# BREAKOUT328.net
KiCad netlist of a schematic drawn in EAGLE
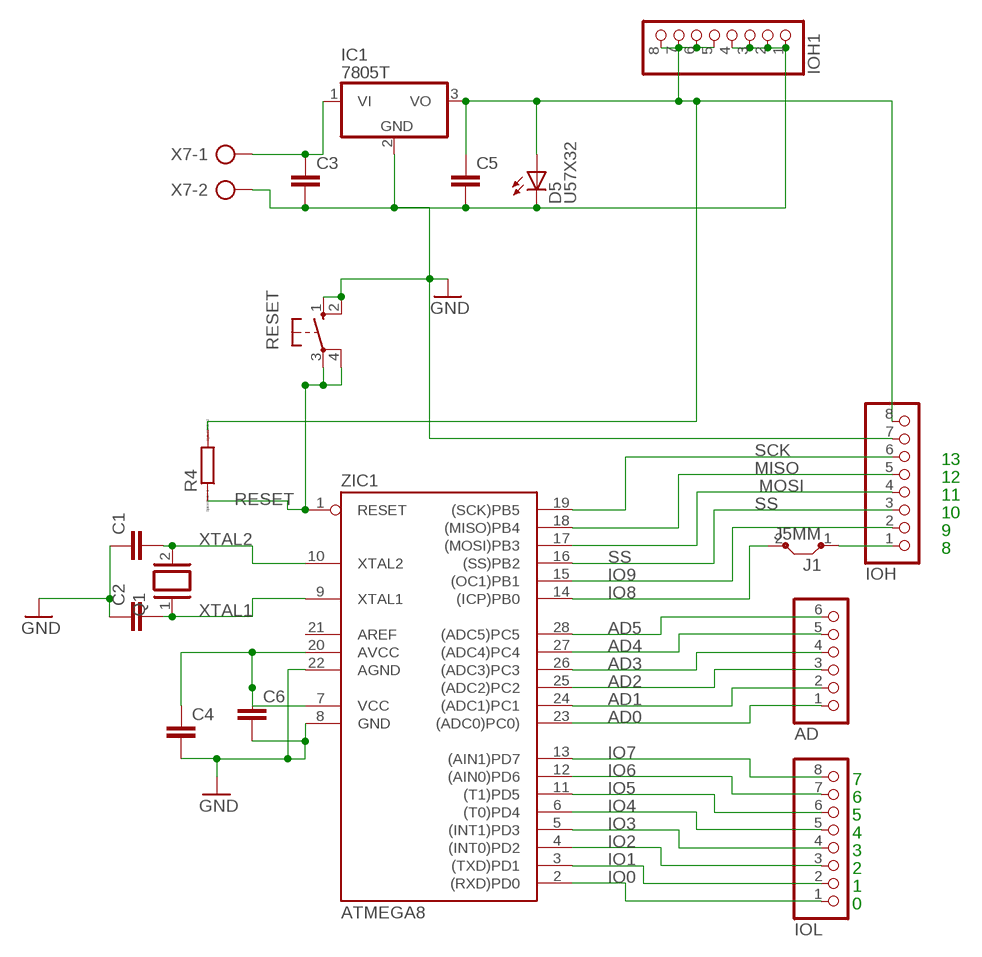
[diagram p0: schematic, sheet 1]

(export (version "E")
  (design (tool "Eeschema 10.0.6"))
  (components
    (comp (ref "AD")
      (value "PINHD-1X6")
      (footprint "eagle-import:1X06")
      (libsource (lib "eagle-import") (part "PINHD-1X6"))
    )
    (comp (ref "C1")
      (value "C2.5/6")
      (footprint "eagle-import:C2.5-6")
      (libsource (lib "eagle-import") (part "C2.5/6"))
    )
    (comp (ref "C2")
      (value "C2.5/6")
      (footprint "eagle-import:C2.5-6")
      (libsource (lib "eagle-import") (part "C2.5/6"))
    )
    (comp (ref "C3")
      (value "C2.5/4")
      (footprint "eagle-import:C2.5-4")
      (libsource (lib "eagle-import") (part "C2.5/4"))
    )
    (comp (ref "C4")
      (value "C2.5/4")
      (footprint "eagle-import:C2.5-4")
      (libsource (lib "eagle-import") (part "C2.5/4"))
    )
    (comp (ref "C5")
      (value "C2.5/4")
      (footprint "eagle-import:C2.5-4")
      (libsource (lib "eagle-import") (part "C2.5/4"))
    )
    (comp (ref "C6")
      (value "C2.5/4")
      (footprint "eagle-import:C2.5-4")
      (libsource (lib "eagle-import") (part "C2.5/4"))
    )
    (comp (ref "D5")
      (value "U57X32")
      (footprint "eagle-import:U57X32")
      (libsource (lib "eagle-import") (part "U57X32"))
    )
    (comp (ref "IC1")
      (value "7805T")
      (footprint "eagle-import:TO220H")
      (libsource (lib "eagle-import") (part "78T05"))
    )
    (comp (ref "IOH")
      (value "PINHD-1X8")
      (footprint "eagle-import:1X08")
      (libsource (lib "eagle-import") (part "PINHD-1X8"))
    )
    (comp (ref "IOH1")
      (value "PINHD-1X8")
      (footprint "eagle-import:1X08")
      (libsource (lib "eagle-import") (part "PINHD-1X8"))
    )
    (comp (ref "IOL")
      (value "PINHD-1X8")
      (footprint "eagle-import:1X08")
      (libsource (lib "eagle-import") (part "PINHD-1X8"))
    )
    (comp (ref "J1")
      (value "J5MM")
      (footprint "eagle-import:05")
      (libsource (lib "eagle-import") (part "J5MM"))
    )
    (comp (ref "Q1")
      (value "XTAL/S")
      (footprint "eagle-import:QS")
      (libsource (lib "eagle-import") (part "XTAL/S"))
    )
    (comp (ref "R4")
      (value "R0207/10")
      (footprint "eagle-import:0207_10")
      (libsource (lib "eagle-import") (part "R0207/10"))
    )
    (comp (ref "RESET")
      (value "10-XX")
      (footprint "eagle-import:B3F-10XX")
      (fields (field (name "MPN") "B3F-1000"))
      (libsource (lib "eagle-import") (part "10-XX"))
    )
    (comp (ref "X7")
      (value "AK500/2-H")
      (footprint "eagle-import:AK500_2-H")
      (libsource (lib "eagle-import") (part "AK500/2-H"))
    )
    (comp (ref "ZIC1")
      (value "ATMEGA8")
      (footprint "eagle-import:DIL28-3")
      (libsource (lib "eagle-import") (part "AT90S4433P"))
    )
  )
  (nets
    (net (code "1") (name "/AD0") (class "Default")
      (node (ref "AD") (pin "1") (pinfunction "1_1") (pintype "passive"))
      (node (ref "ZIC1") (pin "23") (pinfunction "(ADC0)PC0)_23") (pintype "bidirectional"))
    )
    (net (code "2") (name "/AD1") (class "Default")
      (node (ref "AD") (pin "2") (pinfunction "2_2") (pintype "passive"))
      (node (ref "ZIC1") (pin "24") (pinfunction "(ADC1)PC1_24") (pintype "bidirectional"))
    )
    (net (code "3") (name "/AD2") (class "Default")
      (node (ref "AD") (pin "3") (pinfunction "3_3") (pintype "passive"))
      (node (ref "ZIC1") (pin "25") (pinfunction "(ADC2)PC2_25") (pintype "bidirectional"))
    )
    (net (code "4") (name "/AD3") (class "Default")
      (node (ref "AD") (pin "4") (pinfunction "4_4") (pintype "passive"))
      (node (ref "ZIC1") (pin "26") (pinfunction "(ADC3)PC3_26") (pintype "bidirectional"))
    )
    (net (code "5") (name "/AD4") (class "Default")
      (node (ref "AD") (pin "5") (pinfunction "5_5") (pintype "passive"))
      (node (ref "ZIC1") (pin "27") (pinfunction "(ADC4)PC4_27") (pintype "bidirectional"))
    )
    (net (code "6") (name "/AD5") (class "Default")
      (node (ref "AD") (pin "6") (pinfunction "6_6") (pintype "passive"))
      (node (ref "ZIC1") (pin "28") (pinfunction "(ADC5)PC5_28") (pintype "bidirectional"))
    )
    (net (code "7") (name "/IO0") (class "Default")
      (node (ref "IOL") (pin "1") (pinfunction "1_1") (pintype "passive"))
      (node (ref "ZIC1") (pin "2") (pinfunction "(RXD)PD0_2") (pintype "bidirectional"))
    )
    (net (code "8") (name "/IO1") (class "Default")
      (node (ref "IOL") (pin "2") (pinfunction "2_2") (pintype "passive"))
      (node (ref "ZIC1") (pin "3") (pinfunction "(TXD)PD1_3") (pintype "bidirectional"))
    )
    (net (code "9") (name "/IO2") (class "Default")
      (node (ref "IOL") (pin "3") (pinfunction "3_3") (pintype "passive"))
      (node (ref "ZIC1") (pin "4") (pinfunction "(INT0)PD2_4") (pintype "bidirectional"))
    )
    (net (code "10") (name "/IO3") (class "Default")
      (node (ref "IOL") (pin "4") (pinfunction "4_4") (pintype "passive"))
      (node (ref "ZIC1") (pin "5") (pinfunction "(INT1)PD3_5") (pintype "bidirectional"))
    )
    (net (code "11") (name "/IO4") (class "Default")
      (node (ref "IOL") (pin "5") (pinfunction "5_5") (pintype "passive"))
      (node (ref "ZIC1") (pin "6") (pinfunction "(T0)PD4_6") (pintype "bidirectional"))
    )
    (net (code "12") (name "/IO5") (class "Default")
      (node (ref "IOL") (pin "6") (pinfunction "6_6") (pintype "passive"))
      (node (ref "ZIC1") (pin "11") (pinfunction "(T1)PD5_11") (pintype "bidirectional"))
    )
    (net (code "13") (name "/IO6") (class "Default")
      (node (ref "IOL") (pin "7") (pinfunction "7_7") (pintype "passive"))
      (node (ref "ZIC1") (pin "12") (pinfunction "(AIN0)PD6_12") (pintype "bidirectional"))
    )
    (net (code "14") (name "/IO7") (class "Default")
      (node (ref "IOL") (pin "8") (pinfunction "8_8") (pintype "passive"))
      (node (ref "ZIC1") (pin "13") (pinfunction "(AIN1)PD7_13") (pintype "bidirectional"))
    )
    (net (code "15") (name "/IO8") (class "Default")
      (node (ref "J1") (pin "2") (pinfunction "2_2") (pintype "passive"))
      (node (ref "ZIC1") (pin "14") (pinfunction "(ICP)PB0_14") (pintype "bidirectional"))
    )
    (net (code "16") (name "/IO9") (class "Default")
      (node (ref "IOH") (pin "2") (pinfunction "2_2") (pintype "passive"))
      (node (ref "ZIC1") (pin "15") (pinfunction "(OC1)PB1_15") (pintype "bidirectional"))
    )
    (net (code "17") (name "/MISO") (class "Default")
      (node (ref "IOH") (pin "5") (pinfunction "5_5") (pintype "passive"))
      (node (ref "ZIC1") (pin "18") (pinfunction "(MISO)PB4_18") (pintype "bidirectional"))
    )
    (net (code "18") (name "/MOSI") (class "Default")
      (node (ref "IOH") (pin "4") (pinfunction "4_4") (pintype "passive"))
      (node (ref "ZIC1") (pin "17") (pinfunction "(MOSI)PB3_17") (pintype "bidirectional"))
    )
    (net (code "19") (name "/RESET") (class "Default")
      (node (ref "R4") (pin "1") (pinfunction "1_1") (pintype "passive"))
      (node (ref "RESET") (pin "3") (pinfunction "P_3") (pintype "passive"))
      (node (ref "RESET") (pin "4") (pinfunction "P1_4") (pintype "passive"))
      (node (ref "ZIC1") (pin "1") (pinfunction "RESET_1") (pintype "input"))
    )
    (net (code "20") (name "/SCK") (class "Default")
      (node (ref "IOH") (pin "6") (pinfunction "6_6") (pintype "passive"))
      (node (ref "ZIC1") (pin "19") (pinfunction "(SCK)PB5_19") (pintype "bidirectional"))
    )
    (net (code "21") (name "/SS") (class "Default")
      (node (ref "IOH") (pin "3") (pinfunction "3_3") (pintype "passive"))
      (node (ref "ZIC1") (pin "16") (pinfunction "(SS)PB2_16") (pintype "bidirectional"))
    )
    (net (code "22") (name "/VCC") (class "Default")
      (node (ref "C4") (pin "1") (pinfunction "1_1") (pintype "passive"))
      (node (ref "C5") (pin "1") (pinfunction "1_1") (pintype "passive"))
      (node (ref "C6") (pin "1") (pinfunction "1_1") (pintype "passive"))
      (node (ref "D5") (pin "A") (pinfunction "A_A") (pintype "passive"))
      (node (ref "IC1") (pin "3") (pinfunction "VO_3") (pintype "passive"))
      (node (ref "IOH") (pin "8") (pinfunction "8_8") (pintype "passive"))
      (node (ref "IOH1") (pin "5") (pinfunction "5_5") (pintype "passive"))
      (node (ref "IOH1") (pin "6") (pinfunction "6_6") (pintype "passive"))
      (node (ref "IOH1") (pin "7") (pinfunction "7_7") (pintype "passive"))
      (node (ref "IOH1") (pin "8") (pinfunction "8_8") (pintype "passive"))
      (node (ref "R4") (pin "2") (pinfunction "2_2") (pintype "passive"))
      (node (ref "ZIC1") (pin "20") (pinfunction "AVCC_20") (pintype "power_in"))
      (node (ref "ZIC1") (pin "7") (pinfunction "VCC_7") (pintype "power_in"))
    )
    (net (code "23") (name "/XTAL1") (class "Default")
      (node (ref "C2") (pin "2") (pinfunction "2_2") (pintype "passive"))
      (node (ref "Q1") (pin "1") (pinfunction "1_1") (pintype "passive"))
      (node (ref "ZIC1") (pin "9") (pinfunction "XTAL1_9") (pintype "bidirectional"))
    )
    (net (code "24") (name "/XTAL2") (class "Default")
      (node (ref "C1") (pin "2") (pinfunction "2_2") (pintype "passive"))
      (node (ref "Q1") (pin "2") (pinfunction "2_2") (pintype "passive"))
      (node (ref "ZIC1") (pin "10") (pinfunction "XTAL2_10") (pintype "bidirectional"))
    )
    (net (code "25") (name "GND") (class "Default")
      (node (ref "C1") (pin "1") (pinfunction "1_1") (pintype "passive"))
      (node (ref "C2") (pin "1") (pinfunction "1_1") (pintype "passive"))
      (node (ref "C3") (pin "2") (pinfunction "2_2") (pintype "passive"))
      (node (ref "C4") (pin "2") (pinfunction "2_2") (pintype "passive"))
      (node (ref "C5") (pin "2") (pinfunction "2_2") (pintype "passive"))
      (node (ref "C6") (pin "2") (pinfunction "2_2") (pintype "passive"))
      (node (ref "D5") (pin "K") (pinfunction "C_K") (pintype "passive"))
      (node (ref "IC1") (pin "2") (pinfunction "GND_2") (pintype "passive"))
      (node (ref "IOH") (pin "7") (pinfunction "7_7") (pintype "passive"))
      (node (ref "IOH1") (pin "1") (pinfunction "1_1") (pintype "passive"))
      (node (ref "IOH1") (pin "2") (pinfunction "2_2") (pintype "passive"))
      (node (ref "IOH1") (pin "3") (pinfunction "3_3") (pintype "passive"))
      (node (ref "IOH1") (pin "4") (pinfunction "4_4") (pintype "passive"))
      (node (ref "RESET") (pin "1") (pinfunction "S_1") (pintype "passive"))
      (node (ref "RESET") (pin "2") (pinfunction "S1_2") (pintype "passive"))
      (node (ref "X7") (pin "2") (pinfunction "KL_2") (pintype "passive"))
      (node (ref "ZIC1") (pin "22") (pinfunction "AGND_22") (pintype "power_in"))
      (node (ref "ZIC1") (pin "8") (pinfunction "GND_8") (pintype "power_in"))
    )
    (net (code "26") (name "Net-(IC1-VI)") (class "Default")
      (node (ref "C3") (pin "1") (pinfunction "1_1") (pintype "passive"))
      (node (ref "IC1") (pin "1") (pinfunction "VI_1") (pintype "input"))
      (node (ref "X7") (pin "1") (pinfunction "KL_1") (pintype "passive"))
    )
    (net (code "27") (name "Net-(IOH-Pad1)") (class "Default")
      (node (ref "IOH") (pin "1") (pinfunction "1_1") (pintype "passive"))
      (node (ref "J1") (pin "1") (pinfunction "1_1") (pintype "passive"))
    )
    (net (code "28") (name "unconnected-(ZIC1-AREF-Pad21)") (class "Default")
      (node (ref "ZIC1") (pin "21") (pinfunction "AREF_21") (pintype "passive"))
    )
  )
)
